# PCB_Proj.net
KiCad netlist of a schematic drawn in Altium Designer
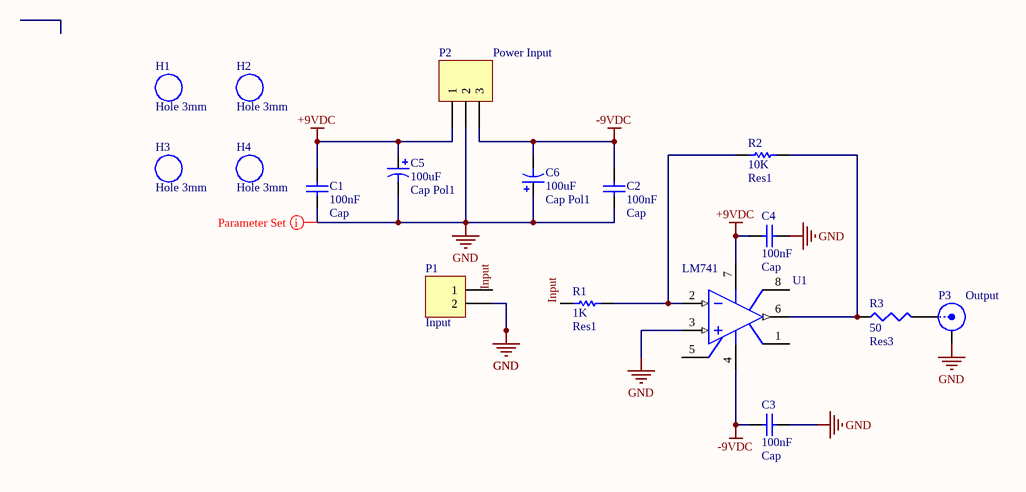
[diagram p0: PCB_Proj.SchDoc]

(export (version "E")
  (design (tool "Eeschema 10.0.6"))
  (components
    (comp (ref "C1")
      (value "Cap")
      (footprint "RAD-0.3")
      (description "Capacitor")
      (fields (field (name "ALTIUM_VALUE") "100nF") (field (name "PUBLISHER") "Altium Limited"))
      (libsource (lib "Miscellaneous Devices") (part "Cap"))
    )
    (comp (ref "C2")
      (value "Cap")
      (footprint "RAD-0.3")
      (description "Capacitor")
      (fields (field (name "ALTIUM_VALUE") "100nF") (field (name "PUBLISHER") "Altium Limited"))
      (libsource (lib "Miscellaneous Devices") (part "Cap"))
    )
    (comp (ref "C3")
      (value "Cap")
      (footprint "RAD-0.3")
      (description "Capacitor")
      (fields (field (name "ALTIUM_VALUE") "100nF") (field (name "PUBLISHER") "Altium Limited"))
      (libsource (lib "Miscellaneous Devices") (part "Cap"))
    )
    (comp (ref "C4")
      (value "Cap")
      (footprint "RAD-0.3")
      (description "Capacitor")
      (fields (field (name "ALTIUM_VALUE") "100nF") (field (name "PUBLISHER") "Altium Limited"))
      (libsource (lib "Miscellaneous Devices") (part "Cap"))
    )
    (comp (ref "C5")
      (value "Cap Pol1")
      (footprint "RB7.6-15")
      (description "Polarized Capacitor (Radial)")
      (fields (field (name "ALTIUM_VALUE") "100uF") (field (name "PUBLISHER") "Altium Limited"))
      (libsource (lib "Miscellaneous Devices") (part "Cap Pol1"))
    )
    (comp (ref "C6")
      (value "Cap Pol1")
      (footprint "RB7.6-15")
      (description "Polarized Capacitor (Radial)")
      (fields (field (name "ALTIUM_VALUE") "100uF") (field (name "PUBLISHER") "Altium Limited"))
      (libsource (lib "Miscellaneous Devices") (part "Cap Pol1"))
    )
    (comp (ref "H1")
      (value "Hole 3mm")
      (footprint "Hole 3mm")
      (libsource (lib "ECE Lib 22") (part "Hole 3mm"))
    )
    (comp (ref "H2")
      (value "Hole 3mm")
      (footprint "Hole 3mm")
      (libsource (lib "ECE Lib 22") (part "Hole 3mm"))
    )
    (comp (ref "H3")
      (value "Hole 3mm")
      (footprint "Hole 3mm")
      (libsource (lib "ECE Lib 22") (part "Hole 3mm"))
    )
    (comp (ref "H4")
      (value "Hole 3mm")
      (footprint "Hole 3mm")
      (libsource (lib "ECE Lib 22") (part "Hole 3mm"))
    )
    (comp (ref "P1")
      (value "Input")
      (footprint "HDR1X2")
      (description "Header, 2-Pin")
      (fields (field (name "PUBLISHER") "Altium Limited"))
      (libsource (lib "Miscellaneous Connectors") (part "Header 2"))
    )
    (comp (ref "P2")
      (value "Power Input")
      (footprint "HDR1X3")
      (description "Header, 3-Pin")
      (fields (field (name "PUBLISHER") "Altium Limited"))
      (libsource (lib "Miscellaneous Connectors") (part "Header 3"))
    )
    (comp (ref "P3")
      (value "Output")
      (footprint "BNC_RA CON")
      (description "BNC Elbow Connector")
      (fields (field (name "PUBLISHER") "Altium Limited"))
      (libsource (lib "Miscellaneous Connectors") (part "BNC"))
    )
    (comp (ref "R1")
      (value "Res1")
      (footprint "AXIAL-0.3")
      (description "Resistor")
      (fields (field (name "ALTIUM_VALUE") "1K") (field (name "PUBLISHER") "Altium Limited"))
      (libsource (lib "Miscellaneous Devices") (part "Res1"))
    )
    (comp (ref "R2")
      (value "Res1")
      (footprint "AXIAL-0.3")
      (description "Resistor")
      (fields (field (name "ALTIUM_VALUE") "10K") (field (name "PUBLISHER") "Altium Limited"))
      (libsource (lib "Miscellaneous Devices") (part "Res1"))
    )
    (comp (ref "R3")
      (value "Res3")
      (footprint "J1-0603")
      (description "Resistor")
      (fields (field (name "ALTIUM_VALUE") "50") (field (name "PUBLISHER") "Altium Limited"))
      (libsource (lib "Miscellaneous Devices") (part "Res3"))
    )
    (comp (ref "U1")
      (value "LM741")
      (footprint "DIP-8")
      (description "FET Operational Amplifier")
      (fields (field (name "PUBLISHER") "Altium Limited"))
      (libsource (lib "Miscellaneous Devices") (part "Op Amp"))
    )
  )
  (nets
    (net (code "1") (name "+9VDC") (class "Default")
      (node (ref "C1") (pin "1") (pinfunction "1_1") (pintype "passive"))
      (node (ref "C4") (pin "2") (pinfunction "2_2") (pintype "passive"))
      (node (ref "C5") (pin "1") (pinfunction "1_1") (pintype "passive"))
      (node (ref "P2") (pin "1") (pinfunction "1_1") (pintype "passive"))
      (node (ref "U1") (pin "7") (pinfunction "V+_7") (pintype "power_in"))
    )
    (net (code "2") (name "-9VDC") (class "Default")
      (node (ref "C2") (pin "1") (pinfunction "1_1") (pintype "passive"))
      (node (ref "C3") (pin "2") (pinfunction "2_2") (pintype "passive"))
      (node (ref "C6") (pin "2") (pinfunction "2_2") (pintype "passive"))
      (node (ref "P2") (pin "3") (pinfunction "3_3") (pintype "passive"))
      (node (ref "U1") (pin "4") (pinfunction "V-_4") (pintype "power_in"))
    )
    (net (code "3") (name "/Input") (class "Default")
      (node (ref "P1") (pin "1") (pinfunction "1_1") (pintype "passive"))
      (node (ref "R1") (pin "1") (pinfunction "1_1") (pintype "passive"))
    )
    (net (code "4") (name "GND") (class "Default")
      (node (ref "C1") (pin "2") (pinfunction "2_2") (pintype "passive"))
      (node (ref "C2") (pin "2") (pinfunction "2_2") (pintype "passive"))
      (node (ref "C3") (pin "1") (pinfunction "1_1") (pintype "passive"))
      (node (ref "C4") (pin "1") (pinfunction "1_1") (pintype "passive"))
      (node (ref "C5") (pin "2") (pinfunction "2_2") (pintype "passive"))
      (node (ref "C6") (pin "1") (pinfunction "1_1") (pintype "passive"))
      (node (ref "P1") (pin "2") (pinfunction "2_2") (pintype "passive"))
      (node (ref "P2") (pin "2") (pinfunction "2_2") (pintype "passive"))
      (node (ref "P3") (pin "2") (pinfunction "Y_2") (pintype "passive"))
      (node (ref "U1") (pin "3") (pinfunction "IN+_3") (pintype "input"))
    )
    (net (code "5") (name "Net-(P3-X)") (class "Default")
      (node (ref "P3") (pin "1") (pinfunction "X_1") (pintype "passive"))
      (node (ref "R3") (pin "2") (pinfunction "2_2") (pintype "passive"))
    )
    (net (code "6") (name "Net-(U1-IN-)") (class "Default")
      (node (ref "R1") (pin "2") (pinfunction "2_2") (pintype "passive"))
      (node (ref "R2") (pin "1") (pinfunction "1_1") (pintype "passive"))
      (node (ref "U1") (pin "2") (pinfunction "IN-_2") (pintype "input"))
    )
    (net (code "7") (name "Net-(U1-OUT)") (class "Default")
      (node (ref "R2") (pin "2") (pinfunction "2_2") (pintype "passive"))
      (node (ref "R3") (pin "1") (pinfunction "1_1") (pintype "passive"))
      (node (ref "U1") (pin "6") (pinfunction "OUT_6") (pintype "output"))
    )
    (net (code "8") (name "unconnected-(U1-OS_NUL-Pad1)") (class "Default")
      (node (ref "U1") (pin "1") (pinfunction "OS_NUL_1") (pintype "passive"))
    )
    (net (code "9") (name "unconnected-(U1-OS_NUL-Pad5)") (class "Default")
      (node (ref "U1") (pin "5") (pinfunction "OS_NUL_5") (pintype "passive"))
    )
    (net (code "10") (name "unconnected-(U1-TAB-Pad8)") (class "Default")
      (node (ref "U1") (pin "8") (pinfunction "TAB_8") (pintype "passive"))
    )
  )
)
